# PCB_2L_-_Revision_History.net
KiCad netlist of a schematic drawn in Altium Designer
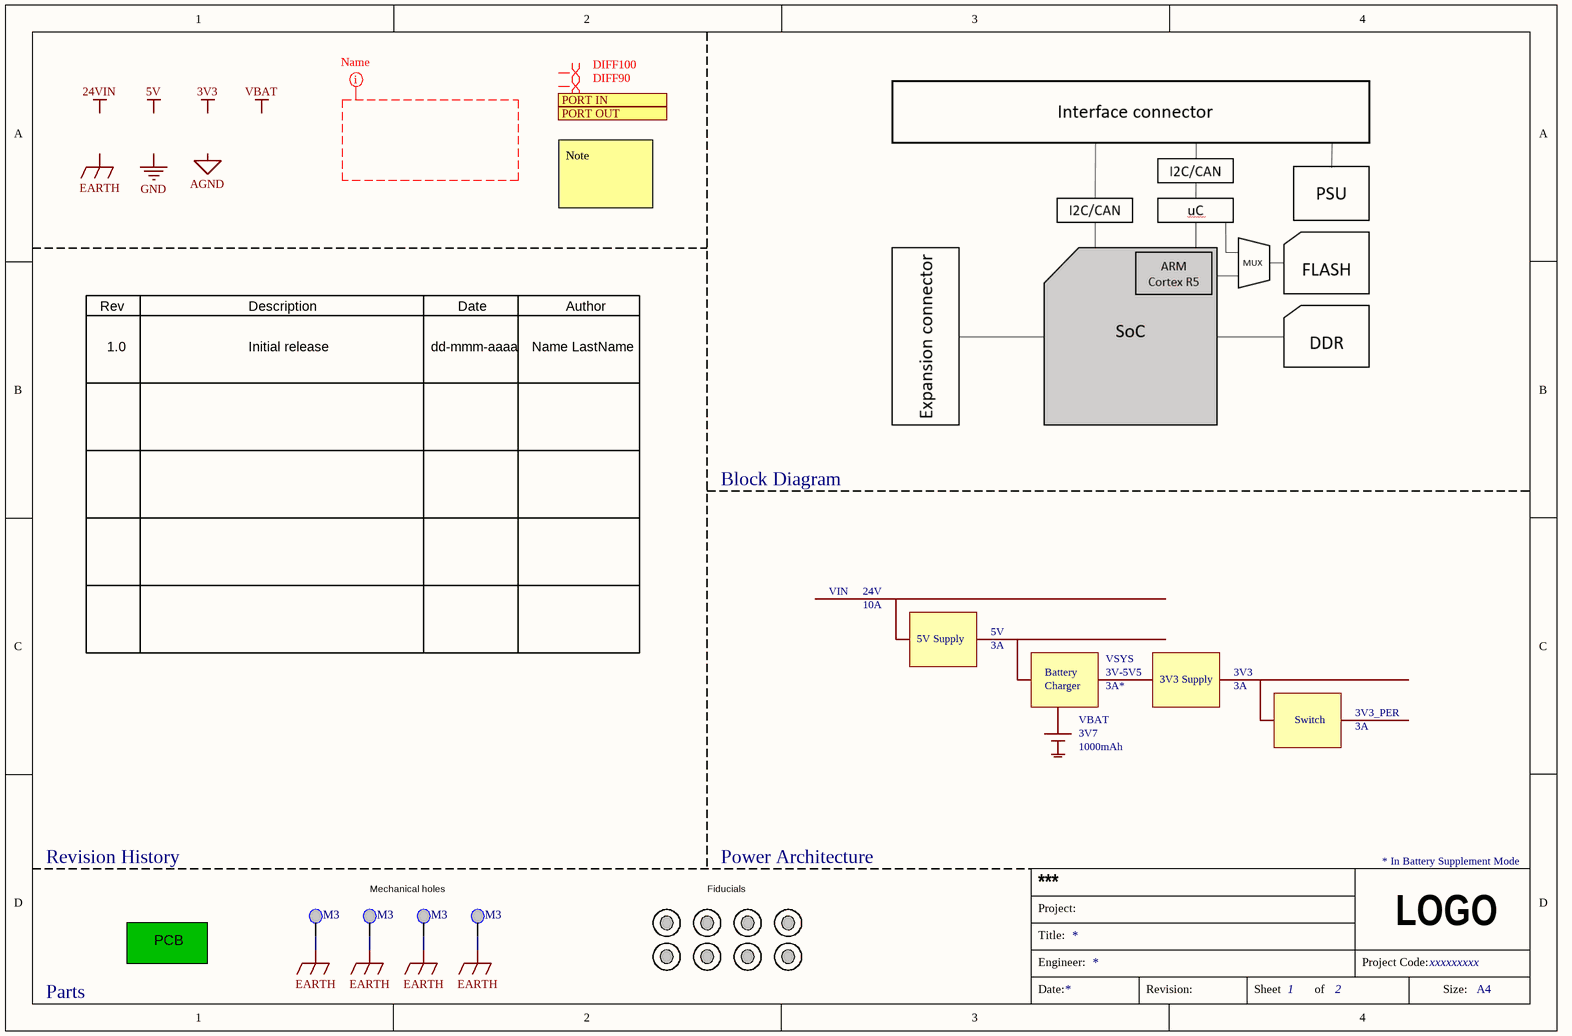
[diagram p0: _PCB_2L - Revision History.SchDoc]

(export (version "E")
  (design (tool "Eeschema 10.0.6"))
  (components
    (comp (ref "FD1")
      (value "Fiducial 1.3")
      (footprint "Fiducial 1.3mm")
      (description "Fiducial 1.3mm")
      (libsource (lib "Miscelaneos") (part "Fiducial 1.3"))
    )
    (comp (ref "FD2")
      (value "Fiducial 1.3")
      (footprint "Fiducial 1.3mm")
      (description "Fiducial 1.3mm")
      (libsource (lib "Miscelaneos") (part "Fiducial 1.3"))
    )
    (comp (ref "FD3")
      (value "Fiducial 1.3")
      (footprint "Fiducial 1.3mm")
      (description "Fiducial 1.3mm")
      (libsource (lib "Miscelaneos") (part "Fiducial 1.3"))
    )
    (comp (ref "FD4")
      (value "Fiducial 1.3")
      (footprint "Fiducial 1.3mm")
      (description "Fiducial 1.3mm")
      (libsource (lib "Miscelaneos") (part "Fiducial 1.3"))
    )
    (comp (ref "FD5")
      (value "Fiducial 1.3")
      (footprint "Fiducial 1.3mm")
      (description "Fiducial 1.3mm")
      (libsource (lib "Miscelaneos") (part "Fiducial 1.3"))
    )
    (comp (ref "FD6")
      (value "Fiducial 1.3")
      (footprint "Fiducial 1.3mm")
      (description "Fiducial 1.3mm")
      (libsource (lib "Miscelaneos") (part "Fiducial 1.3"))
    )
    (comp (ref "FD7")
      (value "Fiducial 1.3")
      (footprint "Fiducial 1.3mm")
      (description "Fiducial 1.3mm")
      (libsource (lib "Miscelaneos") (part "Fiducial 1.3"))
    )
    (comp (ref "FD8")
      (value "Fiducial 1.3")
      (footprint "Fiducial 1.3mm")
      (description "Fiducial 1.3mm")
      (libsource (lib "Miscelaneos") (part "Fiducial 1.3"))
    )
    (comp (ref "MEC1")
      (value "M3")
      (footprint "M3 hole")
      (description "M3 hole")
      (libsource (lib "Miscelaneos") (part "M3 hole"))
    )
    (comp (ref "MEC2")
      (value "M3")
      (footprint "M3 hole")
      (description "M3 hole")
      (libsource (lib "Miscelaneos") (part "M3 hole"))
    )
    (comp (ref "MEC3")
      (value "M3")
      (footprint "M3 hole")
      (description "M3 hole")
      (libsource (lib "Miscelaneos") (part "M3 hole"))
    )
    (comp (ref "MEC4")
      (value "M3")
      (footprint "M3 hole")
      (description "M3 hole")
      (libsource (lib "Miscelaneos") (part "M3 hole"))
    )
    (comp (ref "_PCB1") (value "PCB spec") (description "PCB") (libsource (lib "Miscellaneous") (part "PCB")))
  )
  (nets
    (net (code "7") (name "EARTH") (class "Default")
      (node (ref "MEC1") (pin "0") (pinfunction "0_0") (pintype "passive"))
      (node (ref "MEC2") (pin "0") (pinfunction "0_0") (pintype "passive"))
      (node (ref "MEC3") (pin "0") (pinfunction "0_0") (pintype "passive"))
      (node (ref "MEC4") (pin "0") (pinfunction "0_0") (pintype "passive"))
    )
  )
)
